# Schematic.net
KiCad netlist of a schematic drawn in Altium Designer
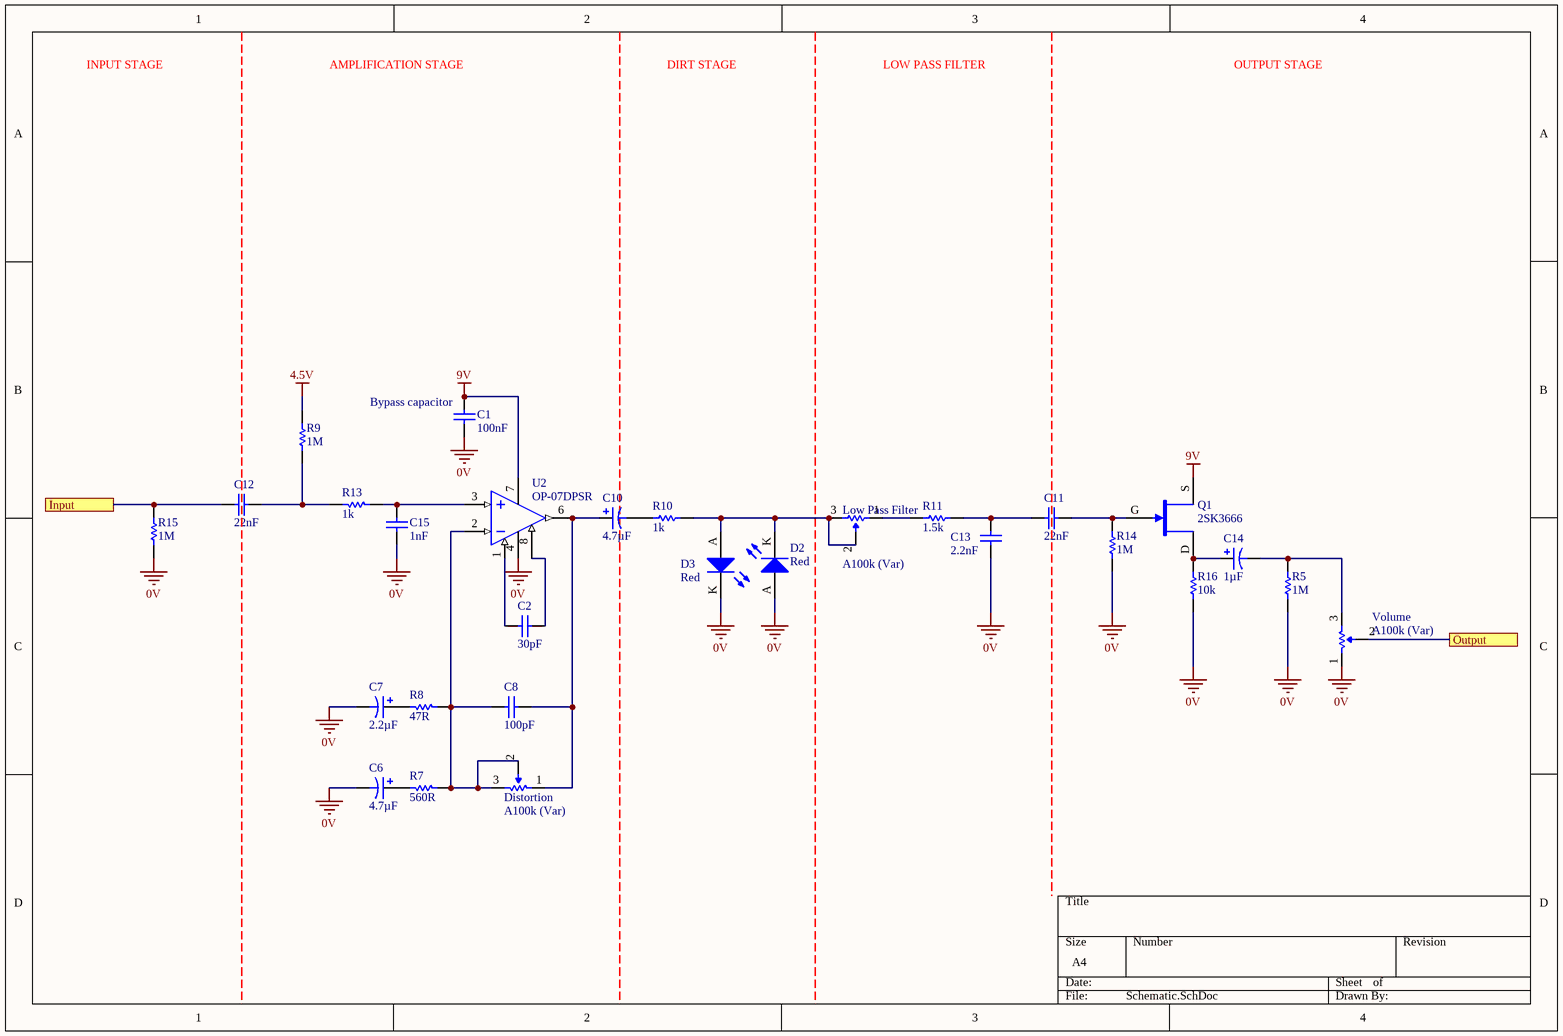
[diagram p0: Schematic.SchDoc]

(export (version "E")
  (design (tool "Eeschema 10.0.6"))
  (components
    (comp (ref "C1")
      (value "100nF")
      (footprint "0805")
      (fields
        (field (name "PART NUMBER") "GCM21BR71H104KA37L")
        (field (name "TOLERANCE") "±10%")
        (field (name "MANUFACTURER") "muRata")
      )
      (libsource (lib "ts_20-standard-library") (part "Capacitor"))
    )
    (comp (ref "C2")
      (value "30pF")
      (footprint "0805")
      (fields
        (field (name "PART NUMBER") "GCM21B5C1H300JA37L")
        (field (name "TOLERANCE") "5%")
        (field (name "MANUFACTURER") "muRata")
      )
      (libsource (lib "ts_20-standard-library") (part "Capacitor"))
    )
    (comp (ref "C6")
      (value "~")
      (footprint "1206")
      (fields
        (field (name "PART NUMBER") "TAJA475K025RNJ")
        (field (name "TOLERANCE") "±10%")
        (field (name "MANUFACTURER") "AVX Corporation")
      )
      (libsource (lib "") (part "Capacitor (Polarised)_1"))
    )
    (comp (ref "C7")
      (value "~")
      (footprint "1206")
      (fields
        (field (name "PART NUMBER") "TAJA225K025RNJ")
        (field (name "TOLERANCE") "±10%")
        (field (name "MANUFACTURER") "AVX Corporation")
      )
      (libsource (lib "") (part "Capacitor (Polarised)_1"))
    )
    (comp (ref "C8")
      (value "100pF")
      (footprint "0805")
      (fields
        (field (name "PART NUMBER") "GCM2165C1H101JA16D")
        (field (name "TOLERANCE") "±5%")
        (field (name "MANUFACTURER") "muRata")
      )
      (libsource (lib "ts_20-standard-library") (part "Capacitor"))
    )
    (comp (ref "C10")
      (value "~")
      (footprint "1206")
      (fields
        (field (name "PART NUMBER") "TAJA475K025RNJ")
        (field (name "TOLERANCE") "±10%")
        (field (name "MANUFACTURER") "AVX Corporation")
      )
      (libsource (lib "ts_20-standard-library") (part "Capacitor (Polarised)"))
    )
    (comp (ref "C11")
      (value "22nF")
      (footprint "0805")
      (fields
        (field (name "PART NUMBER") "GCM21B5C1H223JA16L")
        (field (name "TOLERANCE") "±5%")
        (field (name "MANUFACTURER") "muRata")
      )
      (libsource (lib "ts_20-standard-library") (part "Capacitor"))
    )
    (comp (ref "C12")
      (value "22nF")
      (footprint "0805")
      (fields
        (field (name "PART NUMBER") "GCM21B5C1H223JA16L")
        (field (name "TOLERANCE") "±5%")
        (field (name "MANUFACTURER") "muRata")
      )
      (libsource (lib "ts_20-standard-library") (part "Capacitor"))
    )
    (comp (ref "C13")
      (value "2.2nF")
      (footprint "0805")
      (fields
        (field (name "PART NUMBER") "GCM2165C1H222JA16D")
        (field (name "TOLERANCE") "±5%")
        (field (name "MANUFACTURER") "muRata")
      )
      (libsource (lib "ts_20-standard-library") (part "Capacitor"))
    )
    (comp (ref "C14")
      (value "~")
      (footprint "1206")
      (fields
        (field (name "PART NUMBER") "TAJA105K025RNJ")
        (field (name "TOLERANCE") "±10%")
        (field (name "MANUFACTURER") "AVX Corporation")
      )
      (libsource (lib "ts_20-standard-library") (part "Capacitor (Polarised)"))
    )
    (comp (ref "C15")
      (value "1nF")
      (footprint "0805")
      (fields
        (field (name "PART NUMBER") "GCM2165C1H102JA16D")
        (field (name "TOLERANCE") "±5%")
        (field (name "MANUFACTURER") "muRata")
      )
      (libsource (lib "ts_20-standard-library") (part "Capacitor"))
    )
    (comp (ref "D2")
      (value "Red")
      (footprint "0805 LED")
      (description "Red LED Indication - Discrete 1.75V 0805 (2012 Metric)")
      (fields (field (name "PART NUMBER") "SML-210LTT86") (field (name "MANUFACTURER") "ROHM Semiconductor"))
      (libsource (lib "ts_20-standard-library") (part "LED"))
    )
    (comp (ref "D3")
      (value "Red")
      (footprint "0805 LED")
      (description "Red LED Indication - Discrete 1.75V 0805 (2012 Metric)")
      (fields (field (name "PART NUMBER") "SML-210LTT86") (field (name "MANUFACTURER") "ROHM Semiconductor"))
      (libsource (lib "ts_20-standard-library") (part "LED"))
    )
    (comp (ref "Distortion")
      (value "A100k (Var)")
      (footprint "16mm PCB Mount Pot")
      (fields
        (field (name "PART NUMBER") "502-0317")
        (field (name "MANUFACTURER") "NTE Electronics")
        (field (name "TOLERANCE") "0.2")
      )
      (libsource (lib "ts_20-standard-library") (part "Resistor (Potentiometer)"))
    )
    (comp (ref "Low Pass Filter")
      (value "A100k (Var)")
      (footprint "16mm PCB Mount Pot")
      (fields
        (field (name "PART NUMBER") "502-0317")
        (field (name "MANUFACTURER") "NTE Electronics")
        (field (name "TOLERANCE") "0.2")
      )
      (libsource (lib "ts_20-standard-library") (part "Resistor (Potentiometer)"))
    )
    (comp (ref "Q1")
      (value "2SK3666")
      (footprint "ON SOT-23 JFET")
      (description "JFET N-Channel 10mA 200mW Surface Mount 3-CP")
      (fields
        (field (name "MANUFACTURER") "ON Semiconductor")
        (field (name "DIGIKEY PART NUMBER") "869-1107-1-ND")
        (field (name "PUBLISHER") "Altium Limited")
      )
      (libsource (lib "ts_20-standard-library") (part "JFET-N"))
    )
    (comp (ref "R5")
      (value "1M")
      (footprint "0805")
      (fields
        (field (name "PART NUMBER") "RC0805FR071ML")
        (field (name "MANUFACTURER") "YAGEO")
        (field (name "TOLERANCE") "0.01")
      )
      (libsource (lib "ts_20-standard-library") (part "Resistor"))
    )
    (comp (ref "R7")
      (value "560R")
      (footprint "0805")
      (fields
        (field (name "PART NUMBER") "RC0805FR07560RL")
        (field (name "MANUFACTURER") "YAGEO")
        (field (name "TOLERANCE") "0.01")
      )
      (libsource (lib "ts_20-standard-library") (part "Resistor"))
    )
    (comp (ref "R8")
      (value "47R")
      (footprint "0805")
      (fields
        (field (name "PART NUMBER") "RC0805FR0747RL")
        (field (name "MANUFACTURER") "YAGEO")
        (field (name "TOLERANCE") "0.01")
      )
      (libsource (lib "ts_20-standard-library") (part "Resistor"))
    )
    (comp (ref "R9")
      (value "1M")
      (footprint "0805")
      (fields
        (field (name "PART NUMBER") "RC0805FR071ML")
        (field (name "MANUFACTURER") "YAGEO")
        (field (name "TOLERANCE") "0.01")
      )
      (libsource (lib "ts_20-standard-library") (part "Resistor"))
    )
    (comp (ref "R10")
      (value "1k")
      (footprint "0805")
      (fields
        (field (name "PART NUMBER") "RC0805FR071KL")
        (field (name "MANUFACTURER") "YAGEO")
        (field (name "TOLERANCE") "0.01")
      )
      (libsource (lib "ts_20-standard-library") (part "Resistor"))
    )
    (comp (ref "R11")
      (value "1.5k")
      (footprint "0805")
      (fields
        (field (name "PART NUMBER") "RC0805FR071K5L")
        (field (name "MANUFACTURER") "YAGEO")
        (field (name "TOLERANCE") "0.01")
      )
      (libsource (lib "ts_20-standard-library") (part "Resistor"))
    )
    (comp (ref "R13")
      (value "1k")
      (footprint "0805")
      (fields
        (field (name "PART NUMBER") "RC0805FR071KL")
        (field (name "MANUFACTURER") "YAGEO")
        (field (name "TOLERANCE") "0.01")
      )
      (libsource (lib "ts_20-standard-library") (part "Resistor"))
    )
    (comp (ref "R14")
      (value "1M")
      (footprint "0805")
      (fields
        (field (name "PART NUMBER") "RC0805FR071ML")
        (field (name "MANUFACTURER") "YAGEO")
        (field (name "TOLERANCE") "0.01")
      )
      (libsource (lib "ts_20-standard-library") (part "Resistor"))
    )
    (comp (ref "R15")
      (value "1M")
      (footprint "0805")
      (fields
        (field (name "PART NUMBER") "RC0805FR071ML")
        (field (name "MANUFACTURER") "YAGEO")
        (field (name "TOLERANCE") "0.01")
      )
      (libsource (lib "ts_20-standard-library") (part "Resistor"))
    )
    (comp (ref "R16")
      (value "10k")
      (footprint "0805")
      (fields
        (field (name "PART NUMBER") "RC0805FR0710KL")
        (field (name "MANUFACTURER") "YAGEO")
        (field (name "TOLERANCE") "0.01")
      )
      (libsource (lib "ts_20-standard-library") (part "Resistor"))
    )
    (comp (ref "U2")
      (value "OP-07DPSR")
      (footprint "TI 8-SOIC-W")
      (description "General Purpose Amplifier 1 Circuit 8-SO")
      (fields
        (field (name "MANUFACTURER") "Texas Instruments")
        (field (name "DIGIKEY PART NUMBER") "296-14171-2-ND")
      )
      (libsource (lib "ts_20-standard-library") (part "OP07DP"))
    )
    (comp (ref "Volume")
      (value "A100k (Var)")
      (footprint "16mm PCB Mount Pot")
      (fields
        (field (name "PART NUMBER") "502-0317")
        (field (name "MANUFACTURER") "NTE Electronics")
        (field (name "TOLERANCE") "0.2")
      )
      (libsource (lib "ts_20-standard-library") (part "Resistor (Potentiometer)"))
    )
  )
  (nets
    (net (code "1") (name "/Input") (class "Default")
      (node (ref "C12") (pin "1") (pinfunction "1_1") (pintype "passive"))
      (node (ref "R15") (pin "2") (pinfunction "2_2") (pintype "passive"))
    )
    (net (code "2") (name "/Output") (class "Default")
      (node (ref "Volume") (pin "2") (pinfunction "Wiper_2") (pintype "passive"))
    )
    (net (code "3") (name "0V") (class "Default")
      (node (ref "C1") (pin "1") (pinfunction "1_1") (pintype "passive"))
      (node (ref "C13") (pin "1") (pinfunction "1_1") (pintype "passive"))
      (node (ref "C15") (pin "1") (pinfunction "1_1") (pintype "passive"))
      (node (ref "C6") (pin "1") (pinfunction "1_1") (pintype "passive"))
      (node (ref "C7") (pin "1") (pinfunction "1_1") (pintype "passive"))
      (node (ref "D2") (pin "A") (pinfunction "A_A") (pintype "passive"))
      (node (ref "D3") (pin "K") (pinfunction "K_K") (pintype "passive"))
      (node (ref "R14") (pin "1") (pinfunction "1_1") (pintype "passive"))
      (node (ref "R15") (pin "1") (pinfunction "1_1") (pintype "passive"))
      (node (ref "R16") (pin "1") (pinfunction "1_1") (pintype "passive"))
      (node (ref "R5") (pin "1") (pinfunction "1_1") (pintype "passive"))
      (node (ref "U2") (pin "4") (pinfunction "VCC-_4") (pintype "power_in"))
      (node (ref "Volume") (pin "1") (pinfunction "CCW_1") (pintype "passive"))
    )
    (net (code "4") (name "4.5V") (class "Default")
      (node (ref "R9") (pin "2") (pinfunction "2_2") (pintype "passive"))
    )
    (net (code "5") (name "9V") (class "Default")
      (node (ref "C1") (pin "2") (pinfunction "2_2") (pintype "passive"))
      (node (ref "Q1") (pin "S") (pinfunction "S_S") (pintype "passive"))
      (node (ref "U2") (pin "7") (pinfunction "VCC+_7") (pintype "power_in"))
    )
    (net (code "6") (name "Net-(C6-Pad2)") (class "Default")
      (node (ref "C6") (pin "2") (pinfunction "2_2") (pintype "passive"))
      (node (ref "R7") (pin "1") (pinfunction "1_1") (pintype "passive"))
    )
    (net (code "7") (name "Net-(C7-Pad2)") (class "Default")
      (node (ref "C7") (pin "2") (pinfunction "2_2") (pintype "passive"))
      (node (ref "R8") (pin "1") (pinfunction "1_1") (pintype "passive"))
    )
    (net (code "8") (name "Net-(C10-Pad1)") (class "Default")
      (node (ref "C10") (pin "1") (pinfunction "1_1") (pintype "passive"))
      (node (ref "R10") (pin "1") (pinfunction "1_1") (pintype "passive"))
    )
    (net (code "9") (name "Net-(C11-Pad1)") (class "Default")
      (node (ref "C11") (pin "1") (pinfunction "1_1") (pintype "passive"))
      (node (ref "C13") (pin "2") (pinfunction "2_2") (pintype "passive"))
      (node (ref "R11") (pin "2") (pinfunction "2_2") (pintype "passive"))
    )
    (net (code "10") (name "Net-(C11-Pad2)") (class "Default")
      (node (ref "C11") (pin "2") (pinfunction "2_2") (pintype "passive"))
      (node (ref "Q1") (pin "G") (pinfunction "G_G") (pintype "passive"))
      (node (ref "R14") (pin "2") (pinfunction "2_2") (pintype "passive"))
    )
    (net (code "11") (name "Net-(C12-Pad2)") (class "Default")
      (node (ref "C12") (pin "2") (pinfunction "2_2") (pintype "passive"))
      (node (ref "R13") (pin "1") (pinfunction "1_1") (pintype "passive"))
      (node (ref "R9") (pin "1") (pinfunction "1_1") (pintype "passive"))
    )
    (net (code "12") (name "Net-(C14-Pad2)") (class "Default")
      (node (ref "C14") (pin "2") (pinfunction "2_2") (pintype "passive"))
      (node (ref "Q1") (pin "D") (pinfunction "D_D") (pintype "passive"))
      (node (ref "R16") (pin "2") (pinfunction "2_2") (pintype "passive"))
    )
    (net (code "13") (name "Net-(Distortion-CCW)") (class "Default")
      (node (ref "C10") (pin "2") (pinfunction "2_2") (pintype "passive"))
      (node (ref "C8") (pin "2") (pinfunction "2_2") (pintype "passive"))
      (node (ref "Distortion") (pin "1") (pinfunction "CCW_1") (pintype "passive"))
      (node (ref "U2") (pin "6") (pinfunction "OUT_6") (pintype "output"))
    )
    (net (code "14") (name "Net-(Distortion-CW)") (class "Default")
      (node (ref "C8") (pin "1") (pinfunction "1_1") (pintype "passive"))
      (node (ref "Distortion") (pin "2") (pinfunction "Wiper_2") (pintype "passive"))
      (node (ref "Distortion") (pin "3") (pinfunction "CW_3") (pintype "passive"))
      (node (ref "R7") (pin "2") (pinfunction "2_2") (pintype "passive"))
      (node (ref "R8") (pin "2") (pinfunction "2_2") (pintype "passive"))
      (node (ref "U2") (pin "2") (pinfunction "IN-_2") (pintype "input"))
    )
    (net (code "15") (name "Net-(Low Pass Filter-CCW)") (class "Default")
      (node (ref "Low Pass Filter") (pin "1") (pinfunction "CCW_1") (pintype "passive"))
      (node (ref "R11") (pin "1") (pinfunction "1_1") (pintype "passive"))
    )
    (net (code "16") (name "Net-(Low Pass Filter-CW)") (class "Default")
      (node (ref "D2") (pin "K") (pinfunction "K_K") (pintype "passive"))
      (node (ref "D3") (pin "A") (pinfunction "A_A") (pintype "passive"))
      (node (ref "Low Pass Filter") (pin "2") (pinfunction "Wiper_2") (pintype "passive"))
      (node (ref "Low Pass Filter") (pin "3") (pinfunction "CW_3") (pintype "passive"))
      (node (ref "R10") (pin "2") (pinfunction "2_2") (pintype "passive"))
    )
    (net (code "17") (name "Net-(U2-IN+)") (class "Default")
      (node (ref "C15") (pin "2") (pinfunction "2_2") (pintype "passive"))
      (node (ref "R13") (pin "2") (pinfunction "2_2") (pintype "passive"))
      (node (ref "U2") (pin "3") (pinfunction "IN+_3") (pintype "input"))
    )
    (net (code "18") (name "Net-(U2-OFFSET_N1)") (class "Default")
      (node (ref "C2") (pin "1") (pinfunction "1_1") (pintype "passive"))
      (node (ref "U2") (pin "1") (pinfunction "OFFSET_N1_1") (pintype "input"))
    )
    (net (code "19") (name "Net-(U2-OFFSET_N2)") (class "Default")
      (node (ref "C2") (pin "2") (pinfunction "2_2") (pintype "passive"))
      (node (ref "U2") (pin "8") (pinfunction "OFFSET_N2_8") (pintype "input"))
    )
    (net (code "20") (name "Net-(Volume-CW)") (class "Default")
      (node (ref "C14") (pin "1") (pinfunction "1_1") (pintype "passive"))
      (node (ref "R5") (pin "2") (pinfunction "2_2") (pintype "passive"))
      (node (ref "Volume") (pin "3") (pinfunction "CW_3") (pintype "passive"))
    )
  )
)
